# TopSheet.net
KiCad netlist of a schematic drawn in Altium Designer
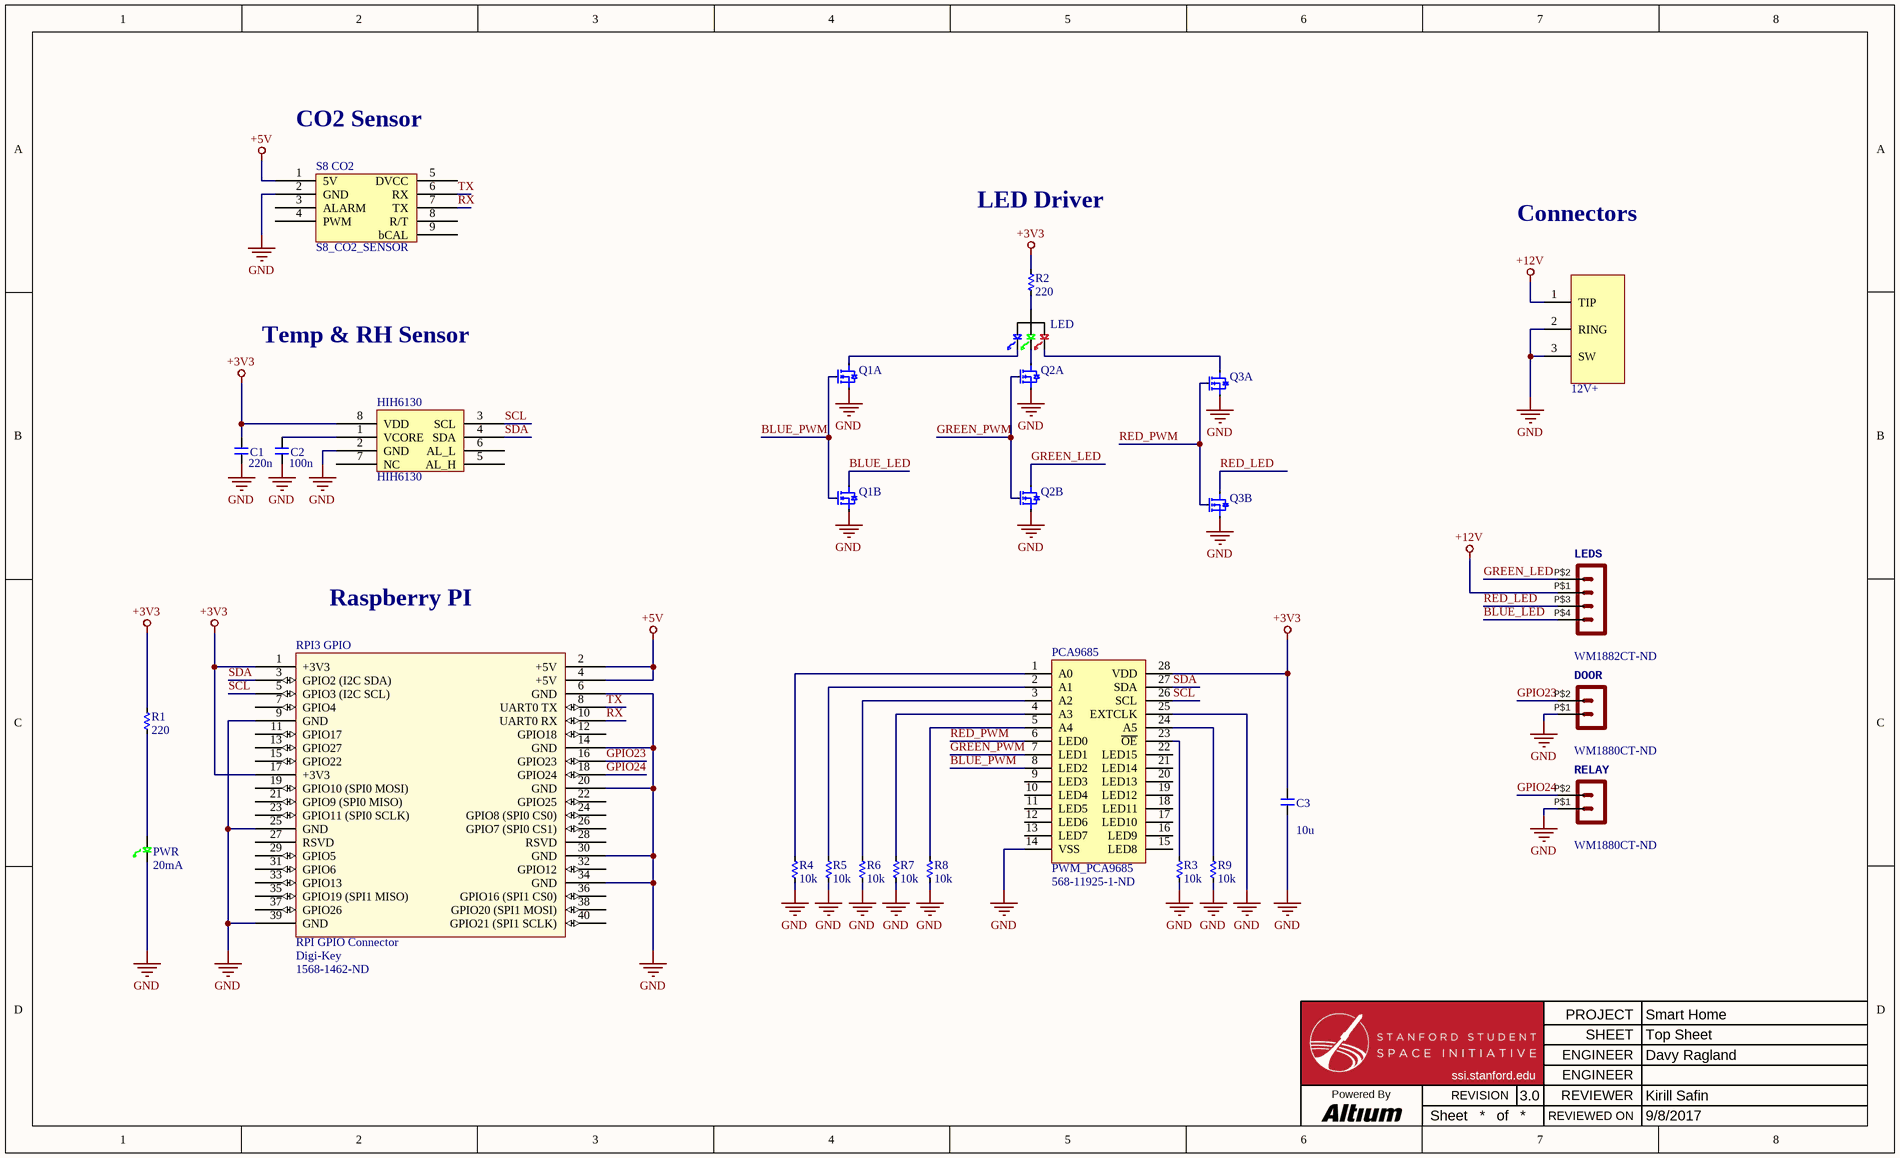
[diagram p0: TopSheet.SchDoc]

(export (version "E")
  (design (tool "Eeschema 10.0.6"))
  (components
    (comp (ref "12V+")
      (value "CONN_BARREL_21X55_PJ-102A")
      (footprint "CUI_21x55_BARREL")
      (description "CONN JACK POWER 2.1MM PCB")
      (fields (field (name "MANUFACTURER") "CUI Inc") (field (name "MANUFACTURER PART NUMBER") "PJ-102A"))
      (libsource (lib "SSI") (part "CONN_BARREL_21X55_PJ-102A"))
    )
    (comp (ref "C1")
      (value "__template_cap")
      (footprint "C0805")
      (fields
        (field (name "VOLTAGE") "16.0")
        (field (name "HUMAN_VALUE") "220n")
        (field (name "TOLERANCE") "10%")
      )
      (libsource (lib "sscp") (part "__template_cap"))
    )
    (comp (ref "C2")
      (value "__template_cap")
      (footprint "C0805")
      (fields
        (field (name "VOLTAGE") "50.0")
        (field (name "HUMAN_VALUE") "100n")
        (field (name "TOLERANCE") "20%")
      )
      (libsource (lib "sscp") (part "__template_cap"))
    )
    (comp (ref "C3")
      (value "__template_cap")
      (footprint "C0805")
      (fields
        (field (name "VOLTAGE") "6.3")
        (field (name "HUMAN_VALUE") "10u")
        (field (name "TOLERANCE") "10%")
      )
      (libsource (lib "sscp") (part "__template_cap"))
    )
    (comp (ref "DOOR")
      (value "Molex - Micro-Fit 3.0 Series connector,  3.00mm (0.118\") pitch header, 2 positions.")
      (footprint "43650-0209")
      (fields
        (field (name "MANUFACTURER") "Molex, LLC")
        (field (name "MANUFACTURER PART NUMBER") "0436500209")
        (field (name "SUPPLIER PART NUMBER 1") "WM1880CT-ND")
      )
      (libsource (lib "con-molex-micro-fit-3_0") (part "HEADER_POS2_?43650-0209"))
    )
    (comp (ref "HIH6130")
      (value "HIH6130")
      (footprint "8SOIC150")
      (description "Humidity Temperature Sensor 0 ~ 100% RH I²C ±4% RH 6s Surface Mount")
      (libsource (lib "SSI") (part "HIH6130"))
    )
    (comp (ref "LED")
      (value "LED_LTST-C19HE1WT")
      (footprint "LED_LITEON_LTST-C19HE1WT")
      (description "LED RGB DIFFUSED 0606")
      (fields
        (field (name "MANUFACTURER") "Lite-On Inc.")
        (field (name "MANUFACTURER PART NUMBER") "LTST-C19HE1WT")
      )
      (libsource (lib "SSI") (part "LED_LTST-C19HE1WT"))
    )
    (comp (ref "LEDS")
      (value "Molex - Micro-Fit 3.0 Series connector,  3.00mm (0.118\") pitch header, 4 positions.")
      (footprint "43650-0409")
      (fields
        (field (name "MANUFACTURER") "Molex, LLC")
        (field (name "MANUFACTURER PART NUMBER") "0436500409")
        (field (name "SUPPLIER PART NUMBER 1") "WM1882CT-ND")
      )
      (libsource (lib "con-molex-micro-fit-3_0") (part "HEADER_POS4_?43650-0409"))
    )
    (comp (ref "PCA9685")
      (value "PWM_PCA9685")
      (footprint "28TSSOP65")
      (fields
        (field (name "MANUFACTURER") "NXP USA Inc.")
        (field (name "MANUFACTURER PART NUMBER") "PCA9685PW,118")
        (field (name "SUPPLIER PART NUMBER 1") "568-11925-1-ND")
      )
      (libsource (lib "SSI") (part "PWM_PCA9685"))
    )
    (comp (ref "PWR")
      (value "LED_LY971")
      (footprint "0805_Diode")
      (description "LED 0805 GREEN 20MA")
      (fields
        (field (name "MANUFACTURER") "OSRAM Opto Semiconductors Inc")
        (field (name "MANUFACTURER PART NUMBER") "LG R971-KN-1")
        (field (name "CURRENT - TEST") "20mA")
      )
      (libsource (lib "SSI") (part "LED_LY971"))
    )
    (comp (ref "Q1")
      (value "NFET_SI7232DN")
      (footprint "POWERPAK_1212-8_DUAL")
      (description "MOSFET 2N-CH 20V 25A PPAK 1212-8")
      (fields
        (field (name "MANUFACTURER") "Vishay Siliconix")
        (field (name "MANUFACTURER PART NUMBER") "SI7232DN-T1-GE3")
      )
      (libsource (lib "SSI") (part "NFET_SI7232DN"))
    )
    (comp (ref "Q2")
      (value "NFET_SI7232DN")
      (footprint "POWERPAK_1212-8_DUAL")
      (description "MOSFET 2N-CH 20V 25A PPAK 1212-8")
      (fields
        (field (name "MANUFACTURER") "Vishay Siliconix")
        (field (name "MANUFACTURER PART NUMBER") "SI7232DN-T1-GE3")
      )
      (libsource (lib "SSI") (part "NFET_SI7232DN"))
    )
    (comp (ref "Q3")
      (value "NFET_SI7232DN")
      (footprint "POWERPAK_1212-8_DUAL")
      (description "MOSFET 2N-CH 20V 25A PPAK 1212-8")
      (fields
        (field (name "MANUFACTURER") "Vishay Siliconix")
        (field (name "MANUFACTURER PART NUMBER") "SI7232DN-T1-GE3")
      )
      (libsource (lib "SSI") (part "NFET_SI7232DN"))
    )
    (comp (ref "R1")
      (value "220")
      (footprint "R0805")
      (fields
        (field (name "MANUFACTURER PART NUMBER") "CRCW0805220RFKEA")
        (field (name "MANUFACTURER") "Vishay Dale")
        (field (name "TOLERANCE") "±1%")
      )
      (libsource (lib "resistor") (part "__template_resistor"))
    )
    (comp (ref "R2")
      (value "220")
      (footprint "R0805")
      (fields
        (field (name "MANUFACTURER PART NUMBER") "CRCW0805220RFKEA")
        (field (name "MANUFACTURER") "Vishay Dale")
        (field (name "TOLERANCE") "±1%")
      )
      (libsource (lib "resistor") (part "__template_resistor"))
    )
    (comp (ref "R3")
      (value "10k")
      (footprint "R0805")
      (fields
        (field (name "MANUFACTURER PART NUMBER") "CRCW080510K0FKEA")
        (field (name "MANUFACTURER") "Vishay Dale")
        (field (name "TOLERANCE") "±1%")
      )
      (libsource (lib "resistor") (part "__template_resistor"))
    )
    (comp (ref "R4")
      (value "10k")
      (footprint "R0805")
      (fields
        (field (name "MANUFACTURER PART NUMBER") "CRCW080510K0FKEA")
        (field (name "MANUFACTURER") "Vishay Dale")
        (field (name "TOLERANCE") "±1%")
      )
      (libsource (lib "resistor") (part "__template_resistor"))
    )
    (comp (ref "R5")
      (value "10k")
      (footprint "R0805")
      (fields
        (field (name "MANUFACTURER PART NUMBER") "CRCW080510K0FKEA")
        (field (name "MANUFACTURER") "Vishay Dale")
        (field (name "TOLERANCE") "±1%")
      )
      (libsource (lib "resistor") (part "__template_resistor"))
    )
    (comp (ref "R6")
      (value "10k")
      (footprint "R0805")
      (fields
        (field (name "MANUFACTURER PART NUMBER") "CRCW080510K0FKEA")
        (field (name "MANUFACTURER") "Vishay Dale")
        (field (name "TOLERANCE") "±1%")
      )
      (libsource (lib "resistor") (part "__template_resistor"))
    )
    (comp (ref "R7")
      (value "10k")
      (footprint "R0805")
      (fields
        (field (name "MANUFACTURER PART NUMBER") "CRCW080510K0FKEA")
        (field (name "MANUFACTURER") "Vishay Dale")
        (field (name "TOLERANCE") "±1%")
      )
      (libsource (lib "resistor") (part "__template_resistor"))
    )
    (comp (ref "R8")
      (value "10k")
      (footprint "R0805")
      (fields
        (field (name "MANUFACTURER PART NUMBER") "CRCW080510K0FKEA")
        (field (name "MANUFACTURER") "Vishay Dale")
        (field (name "TOLERANCE") "±1%")
      )
      (libsource (lib "resistor") (part "__template_resistor"))
    )
    (comp (ref "R9")
      (value "10k")
      (footprint "R0805")
      (fields
        (field (name "MANUFACTURER PART NUMBER") "CRCW080510K0FKEA")
        (field (name "MANUFACTURER") "Vishay Dale")
        (field (name "TOLERANCE") "±1%")
      )
      (libsource (lib "resistor") (part "__template_resistor"))
    )
    (comp (ref "RELAY")
      (value "Molex - Micro-Fit 3.0 Series connector,  3.00mm (0.118\") pitch header, 2 positions.")
      (footprint "43650-0209")
      (fields
        (field (name "MANUFACTURER") "Molex, LLC")
        (field (name "MANUFACTURER PART NUMBER") "0436500209")
        (field (name "SUPPLIER PART NUMBER 1") "WM1880CT-ND")
      )
      (libsource (lib "con-molex-micro-fit-3_0") (part "HEADER_POS2_?43650-0209"))
    )
    (comp (ref "RPI3 GPIO")
      (value "RPI GPIO Connector")
      (footprint "rpi")
      (description "GPIO Header for Raspberry Pi A+/B+/Pi 2/Pi 3 - 2x20")
      (fields
        (field (name "MANUFACTURER") "SparkFun Electronics")
        (field (name "MANUFACTURER PART NUMBER") "PRT-14017")
        (field (name "SUPPLIER 1") "Digi-Key")
        (field (name "SUPPLIER PART NUMBER 1") "1568-1462-ND")
      )
      (libsource (lib "rpi") (part "rpi connector"))
    )
    (comp (ref "S8 CO2")
      (value "S8_CO2_SENSOR")
      (footprint "S8 CO2 SENSOR")
      (libsource (lib "SSI") (part "S8_CO2_SENSOR"))
    )
  )
  (nets
    (net (code "1") (name "+3V3") (class "Default")
      (node (ref "C1") (pin "1") (pintype "passive"))
      (node (ref "C3") (pin "1") (pintype "passive"))
      (node (ref "HIH6130") (pin "8") (pinfunction "VDD_8") (pintype "passive"))
      (node (ref "PCA9685") (pin "28") (pinfunction "VDD_28") (pintype "passive"))
      (node (ref "R1") (pin "1") (pintype "passive"))
      (node (ref "R2") (pin "1") (pintype "passive"))
      (node (ref "RPI3 GPIO") (pin "1") (pinfunction "+3V3_1") (pintype "power_in"))
      (node (ref "RPI3 GPIO") (pin "17") (pinfunction "+3V3_17") (pintype "power_in"))
    )
    (net (code "2") (name "+5V") (class "Default")
      (node (ref "RPI3 GPIO") (pin "2") (pinfunction "+5V_2") (pintype "power_in"))
      (node (ref "RPI3 GPIO") (pin "4") (pinfunction "+5V_4") (pintype "power_in"))
      (node (ref "S8 CO2") (pin "1") (pinfunction "5V_1") (pintype "passive"))
    )
    (net (code "3") (name "+12V") (class "Default")
      (node (ref "12V+") (pin "1") (pinfunction "TIP_1") (pintype "passive"))
      (node (ref "LEDS") (pin "P$1") (pinfunction "2_P$1") (pintype "passive"))
    )
    (net (code "4") (name "/BLUE_LED") (class "Default")
      (node (ref "LEDS") (pin "P$4") (pinfunction "4_P$4") (pintype "passive"))
      (node (ref "Q1") (pin "5") (pintype "passive"))
    )
    (net (code "5") (name "/BLUE_PWM") (class "Default")
      (node (ref "PCA9685") (pin "8") (pinfunction "LED2_8") (pintype "passive"))
      (node (ref "Q1") (pin "2") (pintype "passive"))
      (node (ref "Q1") (pin "4") (pintype "passive"))
    )
    (net (code "6") (name "/GPIO23") (class "Default")
      (node (ref "DOOR") (pin "P$2") (pinfunction "1_P$2") (pintype "passive"))
      (node (ref "RPI3 GPIO") (pin "16") (pinfunction "GPIO23_16") (pintype "bidirectional"))
    )
    (net (code "7") (name "/GPIO24") (class "Default")
      (node (ref "RELAY") (pin "P$2") (pinfunction "1_P$2") (pintype "passive"))
      (node (ref "RPI3 GPIO") (pin "18") (pinfunction "GPIO24_18") (pintype "bidirectional"))
    )
    (net (code "8") (name "/GREEN_LED") (class "Default")
      (node (ref "LEDS") (pin "P$2") (pinfunction "1_P$2") (pintype "passive"))
      (node (ref "Q2") (pin "5") (pintype "passive"))
    )
    (net (code "9") (name "/GREEN_PWM") (class "Default")
      (node (ref "PCA9685") (pin "7") (pinfunction "LED1_7") (pintype "passive"))
      (node (ref "Q2") (pin "2") (pintype "passive"))
      (node (ref "Q2") (pin "4") (pintype "passive"))
    )
    (net (code "10") (name "/RED_LED") (class "Default")
      (node (ref "LEDS") (pin "P$3") (pinfunction "3_P$3") (pintype "passive"))
      (node (ref "Q3") (pin "5") (pintype "passive"))
    )
    (net (code "11") (name "/RED_PWM") (class "Default")
      (node (ref "PCA9685") (pin "6") (pinfunction "LED0_6") (pintype "passive"))
      (node (ref "Q3") (pin "2") (pintype "passive"))
      (node (ref "Q3") (pin "4") (pintype "passive"))
    )
    (net (code "12") (name "/RX") (class "Default")
      (node (ref "RPI3 GPIO") (pin "10") (pinfunction "UART0_RX_10") (pintype "bidirectional"))
      (node (ref "S8 CO2") (pin "7") (pinfunction "TX_7") (pintype "passive"))
    )
    (net (code "13") (name "/SCL") (class "Default")
      (node (ref "HIH6130") (pin "3") (pinfunction "SCL_3") (pintype "passive"))
      (node (ref "PCA9685") (pin "26") (pinfunction "SCL_26") (pintype "passive"))
      (node (ref "RPI3 GPIO") (pin "5") (pinfunction "GPIO3_(I2C_SCL)_5") (pintype "bidirectional"))
    )
    (net (code "14") (name "/SDA") (class "Default")
      (node (ref "HIH6130") (pin "4") (pinfunction "SDA_4") (pintype "passive"))
      (node (ref "PCA9685") (pin "27") (pinfunction "SDA_27") (pintype "passive"))
      (node (ref "RPI3 GPIO") (pin "3") (pinfunction "GPIO2_(I2C_SDA)_3") (pintype "bidirectional"))
    )
    (net (code "15") (name "/TX") (class "Default")
      (node (ref "RPI3 GPIO") (pin "8") (pinfunction "UART0_TX_8") (pintype "bidirectional"))
      (node (ref "S8 CO2") (pin "6") (pinfunction "RX_6") (pintype "passive"))
    )
    (net (code "16") (name "GND") (class "Default")
      (node (ref "12V+") (pin "2") (pinfunction "RING_2") (pintype "passive"))
      (node (ref "12V+") (pin "3") (pinfunction "SW_3") (pintype "passive"))
      (node (ref "C1") (pin "2") (pintype "passive"))
      (node (ref "C2") (pin "2") (pintype "passive"))
      (node (ref "C3") (pin "2") (pintype "passive"))
      (node (ref "DOOR") (pin "P$1") (pinfunction "2_P$1") (pintype "passive"))
      (node (ref "HIH6130") (pin "2") (pinfunction "GND_2") (pintype "passive"))
      (node (ref "PCA9685") (pin "14") (pinfunction "VSS_14") (pintype "passive"))
      (node (ref "PCA9685") (pin "25") (pinfunction "EXTCLK_25") (pintype "passive"))
      (node (ref "PWR") (pin "1") (pintype "passive"))
      (node (ref "Q1") (pin "1") (pintype "passive"))
      (node (ref "Q1") (pin "3") (pintype "passive"))
      (node (ref "Q2") (pin "1") (pintype "passive"))
      (node (ref "Q2") (pin "3") (pintype "passive"))
      (node (ref "Q3") (pin "1") (pintype "passive"))
      (node (ref "Q3") (pin "3") (pintype "passive"))
      (node (ref "R3") (pin "2") (pintype "passive"))
      (node (ref "R4") (pin "2") (pintype "passive"))
      (node (ref "R5") (pin "2") (pintype "passive"))
      (node (ref "R6") (pin "2") (pintype "passive"))
      (node (ref "R7") (pin "2") (pintype "passive"))
      (node (ref "R8") (pin "2") (pintype "passive"))
      (node (ref "R9") (pin "2") (pintype "passive"))
      (node (ref "RELAY") (pin "P$1") (pinfunction "2_P$1") (pintype "passive"))
      (node (ref "RPI3 GPIO") (pin "14") (pinfunction "GND_14") (pintype "power_in"))
      (node (ref "RPI3 GPIO") (pin "20") (pinfunction "GND_20") (pintype "power_in"))
      (node (ref "RPI3 GPIO") (pin "25") (pinfunction "GND_25") (pintype "power_in"))
      (node (ref "RPI3 GPIO") (pin "30") (pinfunction "GND_30") (pintype "power_in"))
      (node (ref "RPI3 GPIO") (pin "34") (pinfunction "GND_34") (pintype "passive"))
      (node (ref "RPI3 GPIO") (pin "39") (pinfunction "GND_39") (pintype "power_in"))
      (node (ref "RPI3 GPIO") (pin "6") (pinfunction "GND_6") (pintype "power_in"))
      (node (ref "RPI3 GPIO") (pin "9") (pinfunction "GND_9") (pintype "power_in"))
      (node (ref "S8 CO2") (pin "2") (pinfunction "GND_2") (pintype "passive"))
    )
    (net (code "17") (name "Net-(HIH6130-VCORE)") (class "Default")
      (node (ref "C2") (pin "1") (pintype "passive"))
      (node (ref "HIH6130") (pin "1") (pinfunction "VCORE_1") (pintype "passive"))
    )
    (net (code "18") (name "Net-(LED-Pad1)") (class "Default")
      (node (ref "LED") (pin "1") (pintype "passive"))
      (node (ref "Q3") (pin "7") (pintype "passive"))
    )
    (net (code "19") (name "Net-(LED-Pad2)") (class "Default")
      (node (ref "LED") (pin "2") (pintype "passive"))
      (node (ref "Q2") (pin "7") (pintype "passive"))
    )
    (net (code "20") (name "Net-(LED-Pad3)") (class "Default")
      (node (ref "LED") (pin "3") (pintype "passive"))
      (node (ref "Q1") (pin "7") (pintype "passive"))
    )
    (net (code "21") (name "Net-(LED-Pad4)") (class "Default")
      (node (ref "LED") (pin "4") (pintype "passive"))
      (node (ref "R2") (pin "2") (pintype "passive"))
    )
    (net (code "22") (name "Net-(PCA9685-A0)") (class "Default")
      (node (ref "PCA9685") (pin "1") (pinfunction "A0_1") (pintype "passive"))
      (node (ref "R4") (pin "1") (pintype "passive"))
    )
    (net (code "23") (name "Net-(PCA9685-A1)") (class "Default")
      (node (ref "PCA9685") (pin "2") (pinfunction "A1_2") (pintype "passive"))
      (node (ref "R5") (pin "1") (pintype "passive"))
    )
    (net (code "24") (name "Net-(PCA9685-A2)") (class "Default")
      (node (ref "PCA9685") (pin "3") (pinfunction "A2_3") (pintype "passive"))
      (node (ref "R6") (pin "1") (pintype "passive"))
    )
    (net (code "25") (name "Net-(PCA9685-A3)") (class "Default")
      (node (ref "PCA9685") (pin "4") (pinfunction "A3_4") (pintype "passive"))
      (node (ref "R7") (pin "1") (pintype "passive"))
    )
    (net (code "26") (name "Net-(PCA9685-A4)") (class "Default")
      (node (ref "PCA9685") (pin "5") (pinfunction "A4_5") (pintype "passive"))
      (node (ref "R8") (pin "1") (pintype "passive"))
    )
    (net (code "27") (name "Net-(PCA9685-A5)") (class "Default")
      (node (ref "PCA9685") (pin "24") (pinfunction "A5_24") (pintype "passive"))
      (node (ref "R9") (pin "1") (pintype "passive"))
    )
    (net (code "28") (name "Net-(PCA9685-~{OE})") (class "Default")
      (node (ref "PCA9685") (pin "23") (pinfunction "~{OE}_23") (pintype "passive"))
      (node (ref "R3") (pin "1") (pintype "passive"))
    )
    (net (code "29") (name "Net-(PWR-Pad2)") (class "Default")
      (node (ref "PWR") (pin "2") (pintype "passive"))
      (node (ref "R1") (pin "2") (pintype "passive"))
    )
    (net (code "30") (name "unconnected-(HIH6130-AL_H-Pad5)") (class "Default")
      (node (ref "HIH6130") (pin "5") (pinfunction "AL_H_5") (pintype "passive"))
    )
    (net (code "31") (name "unconnected-(HIH6130-AL_L-Pad6)") (class "Default")
      (node (ref "HIH6130") (pin "6") (pinfunction "AL_L_6") (pintype "passive"))
    )
    (net (code "32") (name "unconnected-(HIH6130-NC-Pad7)") (class "Default")
      (node (ref "HIH6130") (pin "7") (pinfunction "NC_7") (pintype "passive"))
    )
    (net (code "33") (name "unconnected-(PCA9685-LED3-Pad9)") (class "Default")
      (node (ref "PCA9685") (pin "9") (pinfunction "LED3_9") (pintype "passive"))
    )
    (net (code "34") (name "unconnected-(PCA9685-LED4-Pad10)") (class "Default")
      (node (ref "PCA9685") (pin "10") (pinfunction "LED4_10") (pintype "passive"))
    )
    (net (code "35") (name "unconnected-(PCA9685-LED5-Pad11)") (class "Default")
      (node (ref "PCA9685") (pin "11") (pinfunction "LED5_11") (pintype "passive"))
    )
    (net (code "36") (name "unconnected-(PCA9685-LED6-Pad12)") (class "Default")
      (node (ref "PCA9685") (pin "12") (pinfunction "LED6_12") (pintype "passive"))
    )
    (net (code "37") (name "unconnected-(PCA9685-LED7-Pad13)") (class "Default")
      (node (ref "PCA9685") (pin "13") (pinfunction "LED7_13") (pintype "passive"))
    )
    (net (code "38") (name "unconnected-(PCA9685-LED8-Pad15)") (class "Default")
      (node (ref "PCA9685") (pin "15") (pinfunction "LED8_15") (pintype "passive"))
    )
    (net (code "39") (name "unconnected-(PCA9685-LED9-Pad16)") (class "Default")
      (node (ref "PCA9685") (pin "16") (pinfunction "LED9_16") (pintype "passive"))
    )
    (net (code "40") (name "unconnected-(PCA9685-LED10-Pad17)") (class "Default")
      (node (ref "PCA9685") (pin "17") (pinfunction "LED10_17") (pintype "passive"))
    )
    (net (code "41") (name "unconnected-(PCA9685-LED11-Pad18)") (class "Default")
      (node (ref "PCA9685") (pin "18") (pinfunction "LED11_18") (pintype "passive"))
    )
    (net (code "42") (name "unconnected-(PCA9685-LED12-Pad19)") (class "Default")
      (node (ref "PCA9685") (pin "19") (pinfunction "LED12_19") (pintype "passive"))
    )
    (net (code "43") (name "unconnected-(PCA9685-LED13-Pad20)") (class "Default")
      (node (ref "PCA9685") (pin "20") (pinfunction "LED13_20") (pintype "passive"))
    )
    (net (code "44") (name "unconnected-(PCA9685-LED14-Pad21)") (class "Default")
      (node (ref "PCA9685") (pin "21") (pinfunction "LED14_21") (pintype "passive"))
    )
    (net (code "45") (name "unconnected-(PCA9685-LED15-Pad22)") (class "Default")
      (node (ref "PCA9685") (pin "22") (pinfunction "LED15_22") (pintype "passive"))
    )
    (net (code "46") (name "unconnected-(RPI3 GPIO-GPIO4-Pad7)") (class "Default")
      (node (ref "RPI3 GPIO") (pin "7") (pinfunction "GPIO4_7") (pintype "bidirectional"))
    )
    (net (code "47") (name "unconnected-(RPI3 GPIO-GPIO5-Pad29)") (class "Default")
      (node (ref "RPI3 GPIO") (pin "29") (pinfunction "GPIO5_29") (pintype "bidirectional"))
    )
    (net (code "48") (name "unconnected-(RPI3 GPIO-GPIO6-Pad31)") (class "Default")
      (node (ref "RPI3 GPIO") (pin "31") (pinfunction "GPIO6_31") (pintype "bidirectional"))
    )
    (net (code "49") (name "unconnected-(RPI3 GPIO-GPIO7_(SPI0_CS1)-Pad26)") (class "Default")
      (node (ref "RPI3 GPIO") (pin "26") (pinfunction "GPIO7_(SPI0_CS1)_26") (pintype "bidirectional"))
    )
    (net (code "50") (name "unconnected-(RPI3 GPIO-GPIO8_(SPI0_CS0)-Pad24)") (class "Default")
      (node (ref "RPI3 GPIO") (pin "24") (pinfunction "GPIO8_(SPI0_CS0)_24") (pintype "bidirectional"))
    )
    (net (code "51") (name "unconnected-(RPI3 GPIO-GPIO9_(SPI0_MISO)-Pad21)") (class "Default")
      (node (ref "RPI3 GPIO") (pin "21") (pinfunction "GPIO9_(SPI0_MISO)_21") (pintype "bidirectional"))
    )
    (net (code "52") (name "unconnected-(RPI3 GPIO-GPIO10_(SPI0_MOSI)-Pad19)") (class "Default")
      (node (ref "RPI3 GPIO") (pin "19") (pinfunction "GPIO10_(SPI0_MOSI)_19") (pintype "bidirectional"))
    )
    (net (code "53") (name "unconnected-(RPI3 GPIO-GPIO11_(SPI0_SCLK)-Pad23)") (class "Default")
      (node (ref "RPI3 GPIO") (pin "23") (pinfunction "GPIO11_(SPI0_SCLK)_23") (pintype "bidirectional"))
    )
    (net (code "54") (name "unconnected-(RPI3 GPIO-GPIO12-Pad32)") (class "Default")
      (node (ref "RPI3 GPIO") (pin "32") (pinfunction "GPIO12_32") (pintype "bidirectional"))
    )
    (net (code "55") (name "unconnected-(RPI3 GPIO-GPIO13-Pad33)") (class "Default")
      (node (ref "RPI3 GPIO") (pin "33") (pinfunction "GPIO13_33") (pintype "bidirectional"))
    )
    (net (code "56") (name "unconnected-(RPI3 GPIO-GPIO16_(SPI1_CS0)-Pad36)") (class "Default")
      (node (ref "RPI3 GPIO") (pin "36") (pinfunction "GPIO16_(SPI1_CS0)_36") (pintype "bidirectional"))
    )
    (net (code "57") (name "unconnected-(RPI3 GPIO-GPIO17-Pad11)") (class "Default")
      (node (ref "RPI3 GPIO") (pin "11") (pinfunction "GPIO17_11") (pintype "bidirectional"))
    )
    (net (code "58") (name "unconnected-(RPI3 GPIO-GPIO18-Pad12)") (class "Default")
      (node (ref "RPI3 GPIO") (pin "12") (pinfunction "GPIO18_12") (pintype "bidirectional"))
    )
    (net (code "59") (name "unconnected-(RPI3 GPIO-GPIO19_(SPI1_MISO)-Pad35)") (class "Default")
      (node (ref "RPI3 GPIO") (pin "35") (pinfunction "GPIO19_(SPI1_MISO)_35") (pintype "bidirectional"))
    )
    (net (code "60") (name "unconnected-(RPI3 GPIO-GPIO20_(SPI1_MOSI)-Pad38)") (class "Default")
      (node (ref "RPI3 GPIO") (pin "38") (pinfunction "GPIO20_(SPI1_MOSI)_38") (pintype "bidirectional"))
    )
    (net (code "61") (name "unconnected-(RPI3 GPIO-GPIO21_(SPI1_SCLK)-Pad40)") (class "Default")
      (node (ref "RPI3 GPIO") (pin "40") (pinfunction "GPIO21_(SPI1_SCLK)_40") (pintype "bidirectional"))
    )
    (net (code "62") (name "unconnected-(RPI3 GPIO-GPIO22-Pad15)") (class "Default")
      (node (ref "RPI3 GPIO") (pin "15") (pinfunction "GPIO22_15") (pintype "bidirectional"))
    )
    (net (code "63") (name "unconnected-(RPI3 GPIO-GPIO25-Pad22)") (class "Default")
      (node (ref "RPI3 GPIO") (pin "22") (pinfunction "GPIO25_22") (pintype "bidirectional"))
    )
    (net (code "64") (name "unconnected-(RPI3 GPIO-GPIO26-Pad37)") (class "Default")
      (node (ref "RPI3 GPIO") (pin "37") (pinfunction "GPIO26_37") (pintype "bidirectional"))
    )
    (net (code "65") (name "unconnected-(RPI3 GPIO-GPIO27-Pad13)") (class "Default")
      (node (ref "RPI3 GPIO") (pin "13") (pinfunction "GPIO27_13") (pintype "bidirectional"))
    )
    (net (code "66") (name "unconnected-(RPI3 GPIO-RSVD-Pad27)") (class "Default")
      (node (ref "RPI3 GPIO") (pin "27") (pinfunction "RSVD_27") (pintype "passive"))
    )
    (net (code "67") (name "unconnected-(RPI3 GPIO-RSVD-Pad28)") (class "Default")
      (node (ref "RPI3 GPIO") (pin "28") (pinfunction "RSVD_28") (pintype "passive"))
    )
    (net (code "68") (name "unconnected-(S8 CO2-ALARM-Pad3)") (class "Default")
      (node (ref "S8 CO2") (pin "3") (pinfunction "ALARM_3") (pintype "passive"))
    )
    (net (code "69") (name "unconnected-(S8 CO2-DVCC-Pad5)") (class "Default")
      (node (ref "S8 CO2") (pin "5") (pinfunction "DVCC_5") (pintype "passive"))
    )
    (net (code "70") (name "unconnected-(S8 CO2-PWM-Pad4)") (class "Default")
      (node (ref "S8 CO2") (pin "4") (pinfunction "PWM_4") (pintype "passive"))
    )
    (net (code "71") (name "unconnected-(S8 CO2-R{slash}T-Pad8)") (class "Default")
      (node (ref "S8 CO2") (pin "8") (pinfunction "R/T_8") (pintype "passive"))
    )
    (net (code "72") (name "unconnected-(S8 CO2-bCAL-Pad9)") (class "Default")
      (node (ref "S8 CO2") (pin "9") (pinfunction "bCAL_9") (pintype "passive"))
    )
  )
)
